# umodular_mega_shield_rev02.net
KiCad netlist of a schematic drawn in EAGLE
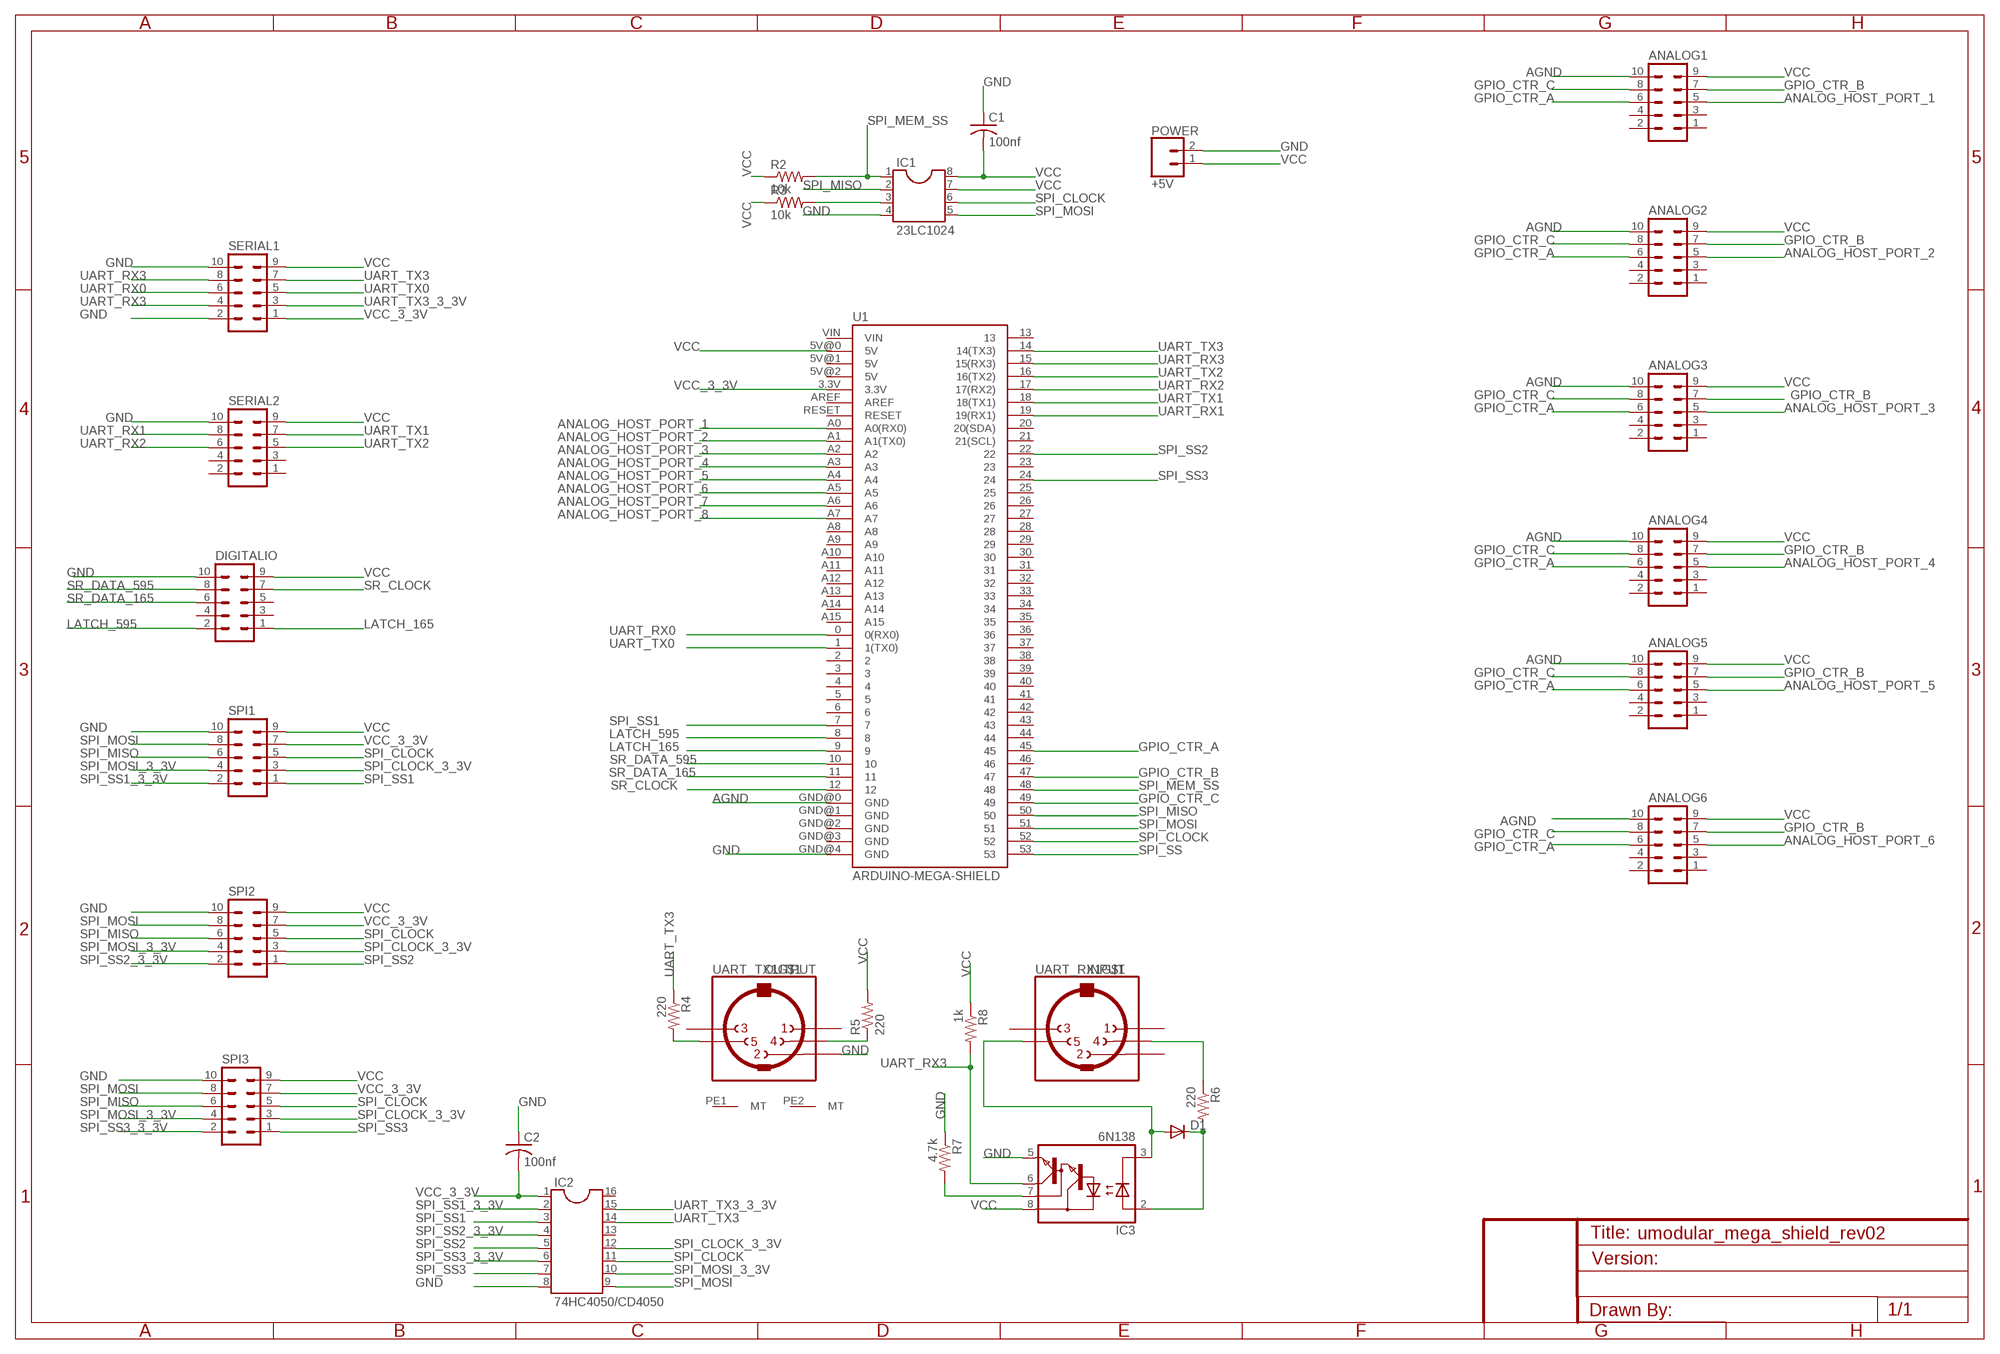
[diagram p0: schematic, sheet 1]

(export (version "E")
  (design (tool "Eeschema 10.0.6"))
  (components
    (comp (ref "ANALOG1")
      (value "MA05-2")
      (footprint "eagle-import:MA05-2")
      (libsource (lib "eagle-import") (part "MA05-2"))
    )
    (comp (ref "ANALOG2")
      (value "MA05-2")
      (footprint "eagle-import:MA05-2")
      (libsource (lib "eagle-import") (part "MA05-2"))
    )
    (comp (ref "ANALOG3")
      (value "MA05-2")
      (footprint "eagle-import:MA05-2")
      (libsource (lib "eagle-import") (part "MA05-2"))
    )
    (comp (ref "ANALOG4")
      (value "MA05-2")
      (footprint "eagle-import:MA05-2")
      (libsource (lib "eagle-import") (part "MA05-2"))
    )
    (comp (ref "ANALOG5")
      (value "MA05-2")
      (footprint "eagle-import:MA05-2")
      (libsource (lib "eagle-import") (part "MA05-2"))
    )
    (comp (ref "ANALOG6")
      (value "MA05-2")
      (footprint "eagle-import:MA05-2")
      (libsource (lib "eagle-import") (part "MA05-2"))
    )
    (comp (ref "C1")
      (value "100nf")
      (footprint "eagle-import:C050-024X044")
      (libsource (lib "eagle-import") (part "C-US050-024X044"))
    )
    (comp (ref "C2")
      (value "100nf")
      (footprint "eagle-import:C050-024X044")
      (libsource (lib "eagle-import") (part "C-US050-024X044"))
    )
    (comp (ref "D1")
      (value "1N4148DO35-7")
      (footprint "eagle-import:DO35-7")
      (libsource (lib "eagle-import") (part "1N4148DO35-7"))
    )
    (comp (ref "DIGITALIO")
      (value "MA05-2")
      (footprint "eagle-import:MA05-2")
      (libsource (lib "eagle-import") (part "MA05-2"))
    )
    (comp (ref "IC1")
      (value "23LC1024")
      (footprint "eagle-import:DIL08")
      (libsource (lib "eagle-import") (part "DIL8"))
    )
    (comp (ref "IC2")
      (value "74HC4050/CD4050")
      (footprint "eagle-import:DIL16")
      (libsource (lib "eagle-import") (part "DIL16"))
    )
    (comp (ref "IC3")
      (value "6N138")
      (footprint "eagle-import:DIL08")
      (fields (field (name "MF") "VISHAY/TELEFUNKEN"))
      (libsource (lib "eagle-import") (part "6N138"))
    )
    (comp (ref "POWER")
      (value "+5V")
      (footprint "eagle-import:1X02_LOCK_LONGPADS")
      (libsource (lib "eagle-import") (part "CONN_02LOCK_LONGPADS"))
    )
    (comp (ref "R2")
      (value "10k")
      (footprint "eagle-import:0204_7@1")
      (libsource (lib "eagle-import") (part "R-US_0204/7"))
    )
    (comp (ref "R3")
      (value "10k")
      (footprint "eagle-import:0204_7@1")
      (libsource (lib "eagle-import") (part "R-US_0204/7"))
    )
    (comp (ref "R4")
      (value "220")
      (footprint "eagle-import:0204_7@1")
      (libsource (lib "eagle-import") (part "R-US_0204/7"))
    )
    (comp (ref "R5")
      (value "220")
      (footprint "eagle-import:0204_7@1")
      (libsource (lib "eagle-import") (part "R-US_0204/7"))
    )
    (comp (ref "R6")
      (value "220")
      (footprint "eagle-import:0204_7@1")
      (libsource (lib "eagle-import") (part "R-US_0204/7"))
    )
    (comp (ref "R7")
      (value "4.7k")
      (footprint "eagle-import:0204_7@1")
      (libsource (lib "eagle-import") (part "R-US_0204/7"))
    )
    (comp (ref "R8")
      (value "1k")
      (footprint "eagle-import:0204_7@1")
      (libsource (lib "eagle-import") (part "R-US_0204/7"))
    )
    (comp (ref "SERIAL1")
      (value "MA05-2")
      (footprint "eagle-import:MA05-2")
      (libsource (lib "eagle-import") (part "MA05-2"))
    )
    (comp (ref "SERIAL2")
      (value "MA05-2")
      (footprint "eagle-import:MA05-2")
      (libsource (lib "eagle-import") (part "MA05-2"))
    )
    (comp (ref "SPI1")
      (value "MA05-2")
      (footprint "eagle-import:MA05-2")
      (libsource (lib "eagle-import") (part "MA05-2"))
    )
    (comp (ref "SPI2")
      (value "MA05-2")
      (footprint "eagle-import:MA05-2")
      (libsource (lib "eagle-import") (part "MA05-2"))
    )
    (comp (ref "SPI3")
      (value "MA05-2")
      (footprint "eagle-import:MA05-2")
      (libsource (lib "eagle-import") (part "MA05-2"))
    )
    (comp (ref "U1")
      (value "ARDUINO-MEGA-SHIELD")
      (footprint "eagle-import:ARDUINO_MEGA@1")
      (libsource (lib "eagle-import") (part "ARDUINO-MEGAFULL"))
    )
    (comp (ref "UART_RX1")
      (value "INPUT")
      (footprint "eagle-import:CP-2350")
      (libsource (lib "eagle-import") (part "MIDIJACK"))
    )
    (comp (ref "UART_TX1")
      (value "OUTPUT")
      (footprint "eagle-import:CP-2350")
      (libsource (lib "eagle-import") (part "MIDIJACK"))
    )
  )
  (nets
    (net (code "1") (name "/AGND") (class "Default")
      (node (ref "ANALOG1") (pin "10") (pinfunction "10_10") (pintype "passive"))
      (node (ref "ANALOG2") (pin "10") (pinfunction "10_10") (pintype "passive"))
      (node (ref "ANALOG3") (pin "10") (pinfunction "10_10") (pintype "passive"))
      (node (ref "ANALOG4") (pin "10") (pinfunction "10_10") (pintype "passive"))
      (node (ref "ANALOG5") (pin "10") (pinfunction "10_10") (pintype "passive"))
      (node (ref "ANALOG6") (pin "10") (pinfunction "10_10") (pintype "passive"))
      (node (ref "U1") (pin "GND@0") (pinfunction "GND_GND@0") (pintype "bidirectional"))
    )
    (net (code "2") (name "/ANALOG_HOST_PORT_1") (class "Default")
      (node (ref "ANALOG1") (pin "5") (pinfunction "5_5") (pintype "passive"))
      (node (ref "U1") (pin "A0") (pinfunction "A0(RX0)_A0") (pintype "bidirectional"))
    )
    (net (code "3") (name "/ANALOG_HOST_PORT_2") (class "Default")
      (node (ref "ANALOG2") (pin "5") (pinfunction "5_5") (pintype "passive"))
      (node (ref "U1") (pin "A1") (pinfunction "A1(TX0)_A1") (pintype "bidirectional"))
    )
    (net (code "4") (name "/ANALOG_HOST_PORT_3") (class "Default")
      (node (ref "ANALOG3") (pin "5") (pinfunction "5_5") (pintype "passive"))
      (node (ref "U1") (pin "A2") (pinfunction "A2_A2") (pintype "bidirectional"))
    )
    (net (code "5") (name "/ANALOG_HOST_PORT_4") (class "Default")
      (node (ref "ANALOG4") (pin "5") (pinfunction "5_5") (pintype "passive"))
      (node (ref "U1") (pin "A3") (pinfunction "A3_A3") (pintype "bidirectional"))
    )
    (net (code "6") (name "/ANALOG_HOST_PORT_5") (class "Default")
      (node (ref "ANALOG5") (pin "5") (pinfunction "5_5") (pintype "passive"))
      (node (ref "U1") (pin "A4") (pinfunction "A4_A4") (pintype "bidirectional"))
    )
    (net (code "7") (name "/ANALOG_HOST_PORT_6") (class "Default")
      (node (ref "ANALOG6") (pin "5") (pinfunction "5_5") (pintype "passive"))
      (node (ref "U1") (pin "A5") (pinfunction "A5_A5") (pintype "bidirectional"))
    )
    (net (code "8") (name "/ANALOG_HOST_PORT_7") (class "Default")
      (node (ref "U1") (pin "A6") (pinfunction "A6_A6") (pintype "bidirectional"))
    )
    (net (code "9") (name "/ANALOG_HOST_PORT_8") (class "Default")
      (node (ref "U1") (pin "A7") (pinfunction "A7_A7") (pintype "bidirectional"))
    )
    (net (code "10") (name "/GND") (class "Default")
      (node (ref "C1") (pin "1") (pinfunction "1_1") (pintype "passive"))
      (node (ref "C2") (pin "1") (pinfunction "1_1") (pintype "passive"))
      (node (ref "DIGITALIO") (pin "10") (pinfunction "10_10") (pintype "passive"))
      (node (ref "IC1") (pin "4") (pinfunction "4_4") (pintype "passive"))
      (node (ref "IC2") (pin "8") (pinfunction "8_8") (pintype "passive"))
      (node (ref "IC3") (pin "5") (pinfunction "GND_5") (pintype "passive"))
      (node (ref "POWER") (pin "2") (pinfunction "2_2") (pintype "passive"))
      (node (ref "R7") (pin "1") (pinfunction "1_1") (pintype "passive"))
      (node (ref "SERIAL1") (pin "10") (pinfunction "10_10") (pintype "passive"))
      (node (ref "SERIAL1") (pin "2") (pinfunction "2_2") (pintype "passive"))
      (node (ref "SERIAL2") (pin "10") (pinfunction "10_10") (pintype "passive"))
      (node (ref "SPI1") (pin "10") (pinfunction "10_10") (pintype "passive"))
      (node (ref "SPI2") (pin "10") (pinfunction "10_10") (pintype "passive"))
      (node (ref "SPI3") (pin "10") (pinfunction "10_10") (pintype "passive"))
      (node (ref "U1") (pin "GND@4") (pinfunction "GND_GND@4") (pintype "bidirectional"))
      (node (ref "UART_TX1") (pin "2") (pinfunction "2_2") (pintype "passive"))
    )
    (net (code "11") (name "/GPIO_CTR_A") (class "Default")
      (node (ref "ANALOG1") (pin "6") (pinfunction "6_6") (pintype "passive"))
      (node (ref "ANALOG2") (pin "6") (pinfunction "6_6") (pintype "passive"))
      (node (ref "ANALOG3") (pin "6") (pinfunction "6_6") (pintype "passive"))
      (node (ref "ANALOG4") (pin "6") (pinfunction "6_6") (pintype "passive"))
      (node (ref "ANALOG5") (pin "6") (pinfunction "6_6") (pintype "passive"))
      (node (ref "ANALOG6") (pin "6") (pinfunction "6_6") (pintype "passive"))
      (node (ref "U1") (pin "45") (pinfunction "45_45") (pintype "bidirectional"))
    )
    (net (code "12") (name "/GPIO_CTR_B") (class "Default")
      (node (ref "ANALOG1") (pin "7") (pinfunction "7_7") (pintype "passive"))
      (node (ref "ANALOG2") (pin "7") (pinfunction "7_7") (pintype "passive"))
      (node (ref "ANALOG3") (pin "7") (pinfunction "7_7") (pintype "passive"))
      (node (ref "ANALOG4") (pin "7") (pinfunction "7_7") (pintype "passive"))
      (node (ref "ANALOG5") (pin "7") (pinfunction "7_7") (pintype "passive"))
      (node (ref "ANALOG6") (pin "7") (pinfunction "7_7") (pintype "passive"))
      (node (ref "U1") (pin "47") (pinfunction "47_47") (pintype "bidirectional"))
    )
    (net (code "13") (name "/GPIO_CTR_C") (class "Default")
      (node (ref "ANALOG1") (pin "8") (pinfunction "8_8") (pintype "passive"))
      (node (ref "ANALOG2") (pin "8") (pinfunction "8_8") (pintype "passive"))
      (node (ref "ANALOG3") (pin "8") (pinfunction "8_8") (pintype "passive"))
      (node (ref "ANALOG4") (pin "8") (pinfunction "8_8") (pintype "passive"))
      (node (ref "ANALOG5") (pin "8") (pinfunction "8_8") (pintype "passive"))
      (node (ref "ANALOG6") (pin "8") (pinfunction "8_8") (pintype "passive"))
      (node (ref "U1") (pin "49") (pinfunction "49_49") (pintype "bidirectional"))
    )
    (net (code "14") (name "/LATCH_165") (class "Default")
      (node (ref "DIGITALIO") (pin "1") (pinfunction "1_1") (pintype "passive"))
      (node (ref "U1") (pin "9") (pinfunction "9_9") (pintype "bidirectional"))
    )
    (net (code "15") (name "/LATCH_595") (class "Default")
      (node (ref "DIGITALIO") (pin "2") (pinfunction "2_2") (pintype "passive"))
      (node (ref "U1") (pin "8") (pinfunction "8_8") (pintype "bidirectional"))
    )
    (net (code "16") (name "/SPI_CLOCK") (class "Default")
      (node (ref "IC1") (pin "6") (pinfunction "6_6") (pintype "passive"))
      (node (ref "IC2") (pin "11") (pinfunction "11_11") (pintype "passive"))
      (node (ref "SPI1") (pin "5") (pinfunction "5_5") (pintype "passive"))
      (node (ref "SPI2") (pin "5") (pinfunction "5_5") (pintype "passive"))
      (node (ref "SPI3") (pin "5") (pinfunction "5_5") (pintype "passive"))
      (node (ref "U1") (pin "52") (pinfunction "52_52") (pintype "bidirectional"))
    )
    (net (code "17") (name "/SPI_CLOCK_3_3V") (class "Default")
      (node (ref "IC2") (pin "12") (pinfunction "12_12") (pintype "passive"))
      (node (ref "SPI1") (pin "3") (pinfunction "3_3") (pintype "passive"))
      (node (ref "SPI2") (pin "3") (pinfunction "3_3") (pintype "passive"))
      (node (ref "SPI3") (pin "3") (pinfunction "3_3") (pintype "passive"))
    )
    (net (code "18") (name "/SPI_MEM_SS") (class "Default")
      (node (ref "IC1") (pin "1") (pinfunction "1_1") (pintype "passive"))
      (node (ref "R2") (pin "2") (pinfunction "2_2") (pintype "passive"))
      (node (ref "U1") (pin "48") (pinfunction "48_48") (pintype "bidirectional"))
    )
    (net (code "19") (name "/SPI_MISO") (class "Default")
      (node (ref "IC1") (pin "2") (pinfunction "2_2") (pintype "passive"))
      (node (ref "SPI1") (pin "6") (pinfunction "6_6") (pintype "passive"))
      (node (ref "SPI2") (pin "6") (pinfunction "6_6") (pintype "passive"))
      (node (ref "SPI3") (pin "6") (pinfunction "6_6") (pintype "passive"))
      (node (ref "U1") (pin "50") (pinfunction "50_50") (pintype "bidirectional"))
    )
    (net (code "20") (name "/SPI_MOSI") (class "Default")
      (node (ref "IC1") (pin "5") (pinfunction "5_5") (pintype "passive"))
      (node (ref "IC2") (pin "9") (pinfunction "9_9") (pintype "passive"))
      (node (ref "SPI1") (pin "8") (pinfunction "8_8") (pintype "passive"))
      (node (ref "SPI2") (pin "8") (pinfunction "8_8") (pintype "passive"))
      (node (ref "SPI3") (pin "8") (pinfunction "8_8") (pintype "passive"))
      (node (ref "U1") (pin "51") (pinfunction "51_51") (pintype "bidirectional"))
    )
    (net (code "21") (name "/SPI_MOSI_3_3V") (class "Default")
      (node (ref "IC2") (pin "10") (pinfunction "10_10") (pintype "passive"))
      (node (ref "SPI1") (pin "4") (pinfunction "4_4") (pintype "passive"))
      (node (ref "SPI2") (pin "4") (pinfunction "4_4") (pintype "passive"))
      (node (ref "SPI3") (pin "4") (pinfunction "4_4") (pintype "passive"))
    )
    (net (code "22") (name "/SPI_SS") (class "Default")
      (node (ref "U1") (pin "53") (pinfunction "53_53") (pintype "bidirectional"))
    )
    (net (code "23") (name "/SPI_SS1") (class "Default")
      (node (ref "IC2") (pin "3") (pinfunction "3_3") (pintype "passive"))
      (node (ref "SPI1") (pin "1") (pinfunction "1_1") (pintype "passive"))
      (node (ref "U1") (pin "7") (pinfunction "7_7") (pintype "bidirectional"))
    )
    (net (code "24") (name "/SPI_SS1_3_3V") (class "Default")
      (node (ref "IC2") (pin "2") (pinfunction "2_2") (pintype "passive"))
      (node (ref "SPI1") (pin "2") (pinfunction "2_2") (pintype "passive"))
    )
    (net (code "25") (name "/SPI_SS2") (class "Default")
      (node (ref "IC2") (pin "5") (pinfunction "5_5") (pintype "passive"))
      (node (ref "SPI2") (pin "1") (pinfunction "1_1") (pintype "passive"))
      (node (ref "U1") (pin "22") (pinfunction "22_22") (pintype "bidirectional"))
    )
    (net (code "26") (name "/SPI_SS2_3_3V") (class "Default")
      (node (ref "IC2") (pin "4") (pinfunction "4_4") (pintype "passive"))
      (node (ref "SPI2") (pin "2") (pinfunction "2_2") (pintype "passive"))
    )
    (net (code "27") (name "/SPI_SS3") (class "Default")
      (node (ref "IC2") (pin "7") (pinfunction "7_7") (pintype "passive"))
      (node (ref "SPI3") (pin "1") (pinfunction "1_1") (pintype "passive"))
      (node (ref "U1") (pin "24") (pinfunction "24_24") (pintype "bidirectional"))
    )
    (net (code "28") (name "/SPI_SS3_3_3V") (class "Default")
      (node (ref "IC2") (pin "6") (pinfunction "6_6") (pintype "passive"))
      (node (ref "SPI3") (pin "2") (pinfunction "2_2") (pintype "passive"))
    )
    (net (code "29") (name "/SR_CLOCK") (class "Default")
      (node (ref "DIGITALIO") (pin "7") (pinfunction "7_7") (pintype "passive"))
      (node (ref "U1") (pin "12") (pinfunction "12_12") (pintype "bidirectional"))
    )
    (net (code "30") (name "/SR_DATA_165") (class "Default")
      (node (ref "DIGITALIO") (pin "6") (pinfunction "6_6") (pintype "passive"))
      (node (ref "U1") (pin "11") (pinfunction "11_11") (pintype "bidirectional"))
    )
    (net (code "31") (name "/SR_DATA_595") (class "Default")
      (node (ref "DIGITALIO") (pin "8") (pinfunction "8_8") (pintype "passive"))
      (node (ref "U1") (pin "10") (pinfunction "10_10") (pintype "bidirectional"))
    )
    (net (code "32") (name "/UART_RX0") (class "Default")
      (node (ref "SERIAL1") (pin "6") (pinfunction "6_6") (pintype "passive"))
      (node (ref "U1") (pin "0") (pinfunction "0(RX0)_0") (pintype "bidirectional"))
    )
    (net (code "33") (name "/UART_RX1") (class "Default")
      (node (ref "SERIAL2") (pin "8") (pinfunction "8_8") (pintype "passive"))
      (node (ref "U1") (pin "19") (pinfunction "19(RX1)_19") (pintype "bidirectional"))
    )
    (net (code "34") (name "/UART_RX2") (class "Default")
      (node (ref "SERIAL2") (pin "6") (pinfunction "6_6") (pintype "passive"))
      (node (ref "U1") (pin "17") (pinfunction "17(RX2)_17") (pintype "bidirectional"))
    )
    (net (code "35") (name "/UART_RX3") (class "Default")
      (node (ref "IC3") (pin "6") (pinfunction "VO_6") (pintype "passive"))
      (node (ref "R8") (pin "2") (pinfunction "2_2") (pintype "passive"))
      (node (ref "SERIAL1") (pin "4") (pinfunction "4_4") (pintype "passive"))
      (node (ref "SERIAL1") (pin "8") (pinfunction "8_8") (pintype "passive"))
      (node (ref "U1") (pin "15") (pinfunction "15(RX3)_15") (pintype "bidirectional"))
    )
    (net (code "36") (name "/UART_TX0") (class "Default")
      (node (ref "SERIAL1") (pin "5") (pinfunction "5_5") (pintype "passive"))
      (node (ref "U1") (pin "1") (pinfunction "1(TX0)_1") (pintype "bidirectional"))
    )
    (net (code "37") (name "/UART_TX1") (class "Default")
      (node (ref "SERIAL2") (pin "7") (pinfunction "7_7") (pintype "passive"))
      (node (ref "U1") (pin "18") (pinfunction "18(TX1)_18") (pintype "bidirectional"))
    )
    (net (code "38") (name "/UART_TX2") (class "Default")
      (node (ref "SERIAL2") (pin "5") (pinfunction "5_5") (pintype "passive"))
      (node (ref "U1") (pin "16") (pinfunction "16(TX2)_16") (pintype "bidirectional"))
    )
    (net (code "39") (name "/UART_TX3") (class "Default")
      (node (ref "IC2") (pin "14") (pinfunction "14_14") (pintype "passive"))
      (node (ref "R4") (pin "1") (pinfunction "1_1") (pintype "passive"))
      (node (ref "SERIAL1") (pin "7") (pinfunction "7_7") (pintype "passive"))
      (node (ref "U1") (pin "14") (pinfunction "14(TX3)_14") (pintype "bidirectional"))
    )
    (net (code "40") (name "/UART_TX3_3_3V") (class "Default")
      (node (ref "IC2") (pin "15") (pinfunction "15_15") (pintype "passive"))
      (node (ref "SERIAL1") (pin "3") (pinfunction "3_3") (pintype "passive"))
    )
    (net (code "41") (name "/VCC") (class "Default")
      (node (ref "ANALOG1") (pin "9") (pinfunction "9_9") (pintype "passive"))
      (node (ref "ANALOG2") (pin "9") (pinfunction "9_9") (pintype "passive"))
      (node (ref "ANALOG3") (pin "9") (pinfunction "9_9") (pintype "passive"))
      (node (ref "ANALOG4") (pin "9") (pinfunction "9_9") (pintype "passive"))
      (node (ref "ANALOG5") (pin "9") (pinfunction "9_9") (pintype "passive"))
      (node (ref "ANALOG6") (pin "9") (pinfunction "9_9") (pintype "passive"))
      (node (ref "C1") (pin "2") (pinfunction "2_2") (pintype "passive"))
      (node (ref "DIGITALIO") (pin "9") (pinfunction "9_9") (pintype "passive"))
      (node (ref "IC1") (pin "7") (pinfunction "7_7") (pintype "passive"))
      (node (ref "IC1") (pin "8") (pinfunction "8_8") (pintype "passive"))
      (node (ref "IC3") (pin "8") (pinfunction "VCC_8") (pintype "passive"))
      (node (ref "POWER") (pin "1") (pinfunction "1_1") (pintype "passive"))
      (node (ref "R2") (pin "1") (pinfunction "1_1") (pintype "passive"))
      (node (ref "R3") (pin "1") (pinfunction "1_1") (pintype "passive"))
      (node (ref "R5") (pin "2") (pinfunction "2_2") (pintype "passive"))
      (node (ref "R8") (pin "1") (pinfunction "1_1") (pintype "passive"))
      (node (ref "SERIAL1") (pin "9") (pinfunction "9_9") (pintype "passive"))
      (node (ref "SERIAL2") (pin "9") (pinfunction "9_9") (pintype "passive"))
      (node (ref "SPI1") (pin "9") (pinfunction "9_9") (pintype "passive"))
      (node (ref "SPI2") (pin "9") (pinfunction "9_9") (pintype "passive"))
      (node (ref "SPI3") (pin "9") (pinfunction "9_9") (pintype "passive"))
      (node (ref "U1") (pin "5V@0") (pinfunction "5V_5V@0") (pintype "bidirectional"))
    )
    (net (code "42") (name "/VCC_3_3V") (class "Default")
      (node (ref "C2") (pin "2") (pinfunction "2_2") (pintype "passive"))
      (node (ref "IC2") (pin "1") (pinfunction "1_1") (pintype "passive"))
      (node (ref "SERIAL1") (pin "1") (pinfunction "1_1") (pintype "passive"))
      (node (ref "SPI1") (pin "7") (pinfunction "7_7") (pintype "passive"))
      (node (ref "SPI2") (pin "7") (pinfunction "7_7") (pintype "passive"))
      (node (ref "SPI3") (pin "7") (pinfunction "7_7") (pintype "passive"))
      (node (ref "U1") (pin "3.3V") (pinfunction "3.3V_3.3V") (pintype "bidirectional"))
    )
    (net (code "43") (name "Net-(IC1-Pad3)") (class "Default")
      (node (ref "IC1") (pin "3") (pinfunction "3_3") (pintype "passive"))
      (node (ref "R3") (pin "2") (pinfunction "2_2") (pintype "passive"))
    )
    (net (code "44") (name "Net-(IC3-A)") (class "Default")
      (node (ref "D1") (pin "C") (pinfunction "C_C") (pintype "passive"))
      (node (ref "IC3") (pin "2") (pinfunction "A_2") (pintype "passive"))
      (node (ref "R6") (pin "2") (pinfunction "2_2") (pintype "passive"))
    )
    (net (code "45") (name "Net-(IC3-C)") (class "Default")
      (node (ref "D1") (pin "A") (pinfunction "A_A") (pintype "passive"))
      (node (ref "IC3") (pin "3") (pinfunction "C_3") (pintype "passive"))
      (node (ref "UART_RX1") (pin "5") (pinfunction "5_5") (pintype "passive"))
    )
    (net (code "46") (name "Net-(IC3-VB)") (class "Default")
      (node (ref "IC3") (pin "7") (pinfunction "VB_7") (pintype "passive"))
      (node (ref "R7") (pin "2") (pinfunction "2_2") (pintype "passive"))
    )
    (net (code "47") (name "Net-(R4-Pad2)") (class "Default")
      (node (ref "R4") (pin "2") (pinfunction "2_2") (pintype "passive"))
      (node (ref "UART_TX1") (pin "5") (pinfunction "5_5") (pintype "passive"))
    )
    (net (code "48") (name "Net-(R5-Pad1)") (class "Default")
      (node (ref "R5") (pin "1") (pinfunction "1_1") (pintype "passive"))
      (node (ref "UART_TX1") (pin "4") (pinfunction "4_4") (pintype "passive"))
    )
    (net (code "49") (name "Net-(R6-Pad1)") (class "Default")
      (node (ref "R6") (pin "1") (pinfunction "1_1") (pintype "passive"))
      (node (ref "UART_RX1") (pin "4") (pinfunction "4_4") (pintype "passive"))
    )
    (net (code "50") (name "unconnected-(ANALOG1-Pad1)") (class "Default")
      (node (ref "ANALOG1") (pin "1") (pinfunction "1_1") (pintype "passive"))
    )
    (net (code "51") (name "unconnected-(ANALOG1-Pad2)") (class "Default")
      (node (ref "ANALOG1") (pin "2") (pinfunction "2_2") (pintype "passive"))
    )
    (net (code "52") (name "unconnected-(ANALOG1-Pad3)") (class "Default")
      (node (ref "ANALOG1") (pin "3") (pinfunction "3_3") (pintype "passive"))
    )
    (net (code "53") (name "unconnected-(ANALOG1-Pad4)") (class "Default")
      (node (ref "ANALOG1") (pin "4") (pinfunction "4_4") (pintype "passive"))
    )
    (net (code "54") (name "unconnected-(ANALOG2-Pad1)") (class "Default")
      (node (ref "ANALOG2") (pin "1") (pinfunction "1_1") (pintype "passive"))
    )
    (net (code "55") (name "unconnected-(ANALOG2-Pad2)") (class "Default")
      (node (ref "ANALOG2") (pin "2") (pinfunction "2_2") (pintype "passive"))
    )
    (net (code "56") (name "unconnected-(ANALOG2-Pad3)") (class "Default")
      (node (ref "ANALOG2") (pin "3") (pinfunction "3_3") (pintype "passive"))
    )
    (net (code "57") (name "unconnected-(ANALOG2-Pad4)") (class "Default")
      (node (ref "ANALOG2") (pin "4") (pinfunction "4_4") (pintype "passive"))
    )
    (net (code "58") (name "unconnected-(ANALOG3-Pad1)") (class "Default")
      (node (ref "ANALOG3") (pin "1") (pinfunction "1_1") (pintype "passive"))
    )
    (net (code "59") (name "unconnected-(ANALOG3-Pad2)") (class "Default")
      (node (ref "ANALOG3") (pin "2") (pinfunction "2_2") (pintype "passive"))
    )
    (net (code "60") (name "unconnected-(ANALOG3-Pad3)") (class "Default")
      (node (ref "ANALOG3") (pin "3") (pinfunction "3_3") (pintype "passive"))
    )
    (net (code "61") (name "unconnected-(ANALOG3-Pad4)") (class "Default")
      (node (ref "ANALOG3") (pin "4") (pinfunction "4_4") (pintype "passive"))
    )
    (net (code "62") (name "unconnected-(ANALOG4-Pad1)") (class "Default")
      (node (ref "ANALOG4") (pin "1") (pinfunction "1_1") (pintype "passive"))
    )
    (net (code "63") (name "unconnected-(ANALOG4-Pad2)") (class "Default")
      (node (ref "ANALOG4") (pin "2") (pinfunction "2_2") (pintype "passive"))
    )
    (net (code "64") (name "unconnected-(ANALOG4-Pad3)") (class "Default")
      (node (ref "ANALOG4") (pin "3") (pinfunction "3_3") (pintype "passive"))
    )
    (net (code "65") (name "unconnected-(ANALOG4-Pad4)") (class "Default")
      (node (ref "ANALOG4") (pin "4") (pinfunction "4_4") (pintype "passive"))
    )
    (net (code "66") (name "unconnected-(ANALOG5-Pad1)") (class "Default")
      (node (ref "ANALOG5") (pin "1") (pinfunction "1_1") (pintype "passive"))
    )
    (net (code "67") (name "unconnected-(ANALOG5-Pad2)") (class "Default")
      (node (ref "ANALOG5") (pin "2") (pinfunction "2_2") (pintype "passive"))
    )
    (net (code "68") (name "unconnected-(ANALOG5-Pad3)") (class "Default")
      (node (ref "ANALOG5") (pin "3") (pinfunction "3_3") (pintype "passive"))
    )
    (net (code "69") (name "unconnected-(ANALOG5-Pad4)") (class "Default")
      (node (ref "ANALOG5") (pin "4") (pinfunction "4_4") (pintype "passive"))
    )
    (net (code "70") (name "unconnected-(ANALOG6-Pad1)") (class "Default")
      (node (ref "ANALOG6") (pin "1") (pinfunction "1_1") (pintype "passive"))
    )
    (net (code "71") (name "unconnected-(ANALOG6-Pad2)") (class "Default")
      (node (ref "ANALOG6") (pin "2") (pinfunction "2_2") (pintype "passive"))
    )
    (net (code "72") (name "unconnected-(ANALOG6-Pad3)") (class "Default")
      (node (ref "ANALOG6") (pin "3") (pinfunction "3_3") (pintype "passive"))
    )
    (net (code "73") (name "unconnected-(ANALOG6-Pad4)") (class "Default")
      (node (ref "ANALOG6") (pin "4") (pinfunction "4_4") (pintype "passive"))
    )
    (net (code "74") (name "unconnected-(DIGITALIO-Pad3)") (class "Default")
      (node (ref "DIGITALIO") (pin "3") (pinfunction "3_3") (pintype "passive"))
    )
    (net (code "75") (name "unconnected-(DIGITALIO-Pad4)") (class "Default")
      (node (ref "DIGITALIO") (pin "4") (pinfunction "4_4") (pintype "passive"))
    )
    (net (code "76") (name "unconnected-(DIGITALIO-Pad5)") (class "Default")
      (node (ref "DIGITALIO") (pin "5") (pinfunction "5_5") (pintype "passive"))
    )
    (net (code "77") (name "unconnected-(IC2-Pad13)") (class "Default")
      (node (ref "IC2") (pin "13") (pinfunction "13_13") (pintype "passive"))
    )
    (net (code "78") (name "unconnected-(IC2-Pad16)") (class "Default")
      (node (ref "IC2") (pin "16") (pinfunction "16_16") (pintype "passive"))
    )
    (net (code "79") (name "unconnected-(SERIAL2-Pad1)") (class "Default")
      (node (ref "SERIAL2") (pin "1") (pinfunction "1_1") (pintype "passive"))
    )
    (net (code "80") (name "unconnected-(SERIAL2-Pad2)") (class "Default")
      (node (ref "SERIAL2") (pin "2") (pinfunction "2_2") (pintype "passive"))
    )
    (net (code "81") (name "unconnected-(SERIAL2-Pad3)") (class "Default")
      (node (ref "SERIAL2") (pin "3") (pinfunction "3_3") (pintype "passive"))
    )
    (net (code "82") (name "unconnected-(SERIAL2-Pad4)") (class "Default")
      (node (ref "SERIAL2") (pin "4") (pinfunction "4_4") (pintype "passive"))
    )
    (net (code "83") (name "unconnected-(U1-5V-Pad5V@1)") (class "Default")
      (node (ref "U1") (pin "5V@1") (pinfunction "5V_5V@1") (pintype "bidirectional"))
    )
    (net (code "84") (name "unconnected-(U1-5V-Pad5V@2)") (class "Default")
      (node (ref "U1") (pin "5V@2") (pinfunction "5V_5V@2") (pintype "bidirectional"))
    )
    (net (code "85") (name "unconnected-(U1-20(SDA)-Pad20)") (class "Default")
      (node (ref "U1") (pin "20") (pinfunction "20(SDA)_20") (pintype "bidirectional"))
    )
    (net (code "86") (name "unconnected-(U1-21(SCL)-Pad21)") (class "Default")
      (node (ref "U1") (pin "21") (pinfunction "21(SCL)_21") (pintype "bidirectional"))
    )
    (net (code "87") (name "unconnected-(U1-GND-PadGND@1)") (class "Default")
      (node (ref "U1") (pin "GND@1") (pinfunction "GND_GND@1") (pintype "bidirectional"))
    )
    (net (code "88") (name "unconnected-(U1-GND-PadGND@2)") (class "Default")
      (node (ref "U1") (pin "GND@2") (pinfunction "GND_GND@2") (pintype "bidirectional"))
    )
    (net (code "89") (name "unconnected-(U1-GND-PadGND@3)") (class "Default")
      (node (ref "U1") (pin "GND@3") (pinfunction "GND_GND@3") (pintype "bidirectional"))
    )
    (net (code "90") (name "unconnected-(U1-Pad2)") (class "Default")
      (node (ref "U1") (pin "2") (pinfunction "2_2") (pintype "bidirectional"))
    )
    (net (code "91") (name "unconnected-(U1-Pad3)") (class "Default")
      (node (ref "U1") (pin "3") (pinfunction "3_3") (pintype "bidirectional"))
    )
    (net (code "92") (name "unconnected-(U1-Pad4)") (class "Default")
      (node (ref "U1") (pin "4") (pinfunction "4_4") (pintype "bidirectional"))
    )
    (net (code "93") (name "unconnected-(U1-Pad5)") (class "Default")
      (node (ref "U1") (pin "5") (pinfunction "5_5") (pintype "bidirectional"))
    )
    (net (code "94") (name "unconnected-(U1-Pad6)") (class "Default")
      (node (ref "U1") (pin "6") (pinfunction "6_6") (pintype "bidirectional"))
    )
    (net (code "95") (name "unconnected-(U1-Pad13)") (class "Default")
      (node (ref "U1") (pin "13") (pinfunction "13_13") (pintype "bidirectional"))
    )
    (net (code "96") (name "unconnected-(U1-Pad23)") (class "Default")
      (node (ref "U1") (pin "23") (pinfunction "23_23") (pintype "bidirectional"))
    )
    (net (code "97") (name "unconnected-(U1-Pad25)") (class "Default")
      (node (ref "U1") (pin "25") (pinfunction "25_25") (pintype "bidirectional"))
    )
    (net (code "98") (name "unconnected-(U1-Pad26)") (class "Default")
      (node (ref "U1") (pin "26") (pinfunction "26_26") (pintype "bidirectional"))
    )
    (net (code "99") (name "unconnected-(U1-Pad27)") (class "Default")
      (node (ref "U1") (pin "27") (pinfunction "27_27") (pintype "bidirectional"))
    )
    (net (code "100") (name "unconnected-(U1-Pad28)") (class "Default")
      (node (ref "U1") (pin "28") (pinfunction "28_28") (pintype "bidirectional"))
    )
    (net (code "101") (name "unconnected-(U1-Pad29)") (class "Default")
      (node (ref "U1") (pin "29") (pinfunction "29_29") (pintype "bidirectional"))
    )
    (net (code "102") (name "unconnected-(U1-Pad30)") (class "Default")
      (node (ref "U1") (pin "30") (pinfunction "30_30") (pintype "bidirectional"))
    )
    (net (code "103") (name "unconnected-(U1-Pad31)") (class "Default")
      (node (ref "U1") (pin "31") (pinfunction "31_31") (pintype "bidirectional"))
    )
    (net (code "104") (name "unconnected-(U1-Pad32)") (class "Default")
      (node (ref "U1") (pin "32") (pinfunction "32_32") (pintype "bidirectional"))
    )
    (net (code "105") (name "unconnected-(U1-Pad33)") (class "Default")
      (node (ref "U1") (pin "33") (pinfunction "33_33") (pintype "bidirectional"))
    )
    (net (code "106") (name "unconnected-(U1-Pad34)") (class "Default")
      (node (ref "U1") (pin "34") (pinfunction "34_34") (pintype "bidirectional"))
    )
    (net (code "107") (name "unconnected-(U1-Pad35)") (class "Default")
      (node (ref "U1") (pin "35") (pinfunction "35_35") (pintype "bidirectional"))
    )
    (net (code "108") (name "unconnected-(U1-Pad36)") (class "Default")
      (node (ref "U1") (pin "36") (pinfunction "36_36") (pintype "bidirectional"))
    )
    (net (code "109") (name "unconnected-(U1-Pad37)") (class "Default")
      (node (ref "U1") (pin "37") (pinfunction "37_37") (pintype "bidirectional"))
    )
    (net (code "110") (name "unconnected-(U1-Pad38)") (class "Default")
      (node (ref "U1") (pin "38") (pinfunction "38_38") (pintype "bidirectional"))
    )
    (net (code "111") (name "unconnected-(U1-Pad39)") (class "Default")
      (node (ref "U1") (pin "39") (pinfunction "39_39") (pintype "bidirectional"))
    )
    (net (code "112") (name "unconnected-(U1-Pad40)") (class "Default")
      (node (ref "U1") (pin "40") (pinfunction "40_40") (pintype "bidirectional"))
    )
    (net (code "113") (name "unconnected-(U1-Pad41)") (class "Default")
      (node (ref "U1") (pin "41") (pinfunction "41_41") (pintype "bidirectional"))
    )
    (net (code "114") (name "unconnected-(U1-Pad42)") (class "Default")
      (node (ref "U1") (pin "42") (pinfunction "42_42") (pintype "bidirectional"))
    )
    (net (code "115") (name "unconnected-(U1-Pad43)") (class "Default")
      (node (ref "U1") (pin "43") (pinfunction "43_43") (pintype "bidirectional"))
    )
    (net (code "116") (name "unconnected-(U1-Pad44)") (class "Default")
      (node (ref "U1") (pin "44") (pinfunction "44_44") (pintype "bidirectional"))
    )
    (net (code "117") (name "unconnected-(U1-Pad46)") (class "Default")
      (node (ref "U1") (pin "46") (pinfunction "46_46") (pintype "bidirectional"))
    )
    (net (code "118") (name "unconnected-(U1-PadA8)") (class "Default")
      (node (ref "U1") (pin "A8") (pinfunction "A8_A8") (pintype "bidirectional"))
    )
    (net (code "119") (name "unconnected-(U1-PadA9)") (class "Default")
      (node (ref "U1") (pin "A9") (pinfunction "A9_A9") (pintype "bidirectional"))
    )
    (net (code "120") (name "unconnected-(U1-PadA10)") (class "Default")
      (node (ref "U1") (pin "A10") (pinfunction "A10_A10") (pintype "bidirectional"))
    )
    (net (code "121") (name "unconnected-(U1-PadA11)") (class "Default")
      (node (ref "U1") (pin "A11") (pinfunction "A11_A11") (pintype "bidirectional"))
    )
    (net (code "122") (name "unconnected-(U1-PadA12)") (class "Default")
      (node (ref "U1") (pin "A12") (pinfunction "A12_A12") (pintype "bidirectional"))
    )
    (net (code "123") (name "unconnected-(U1-PadA13)") (class "Default")
      (node (ref "U1") (pin "A13") (pinfunction "A13_A13") (pintype "bidirectional"))
    )
    (net (code "124") (name "unconnected-(U1-PadA14)") (class "Default")
      (node (ref "U1") (pin "A14") (pinfunction "A14_A14") (pintype "bidirectional"))
    )
    (net (code "125") (name "unconnected-(U1-PadA15)") (class "Default")
      (node (ref "U1") (pin "A15") (pinfunction "A15_A15") (pintype "bidirectional"))
    )
    (net (code "126") (name "unconnected-(U1-PadAREF)") (class "Default")
      (node (ref "U1") (pin "AREF") (pinfunction "AREF_AREF") (pintype "bidirectional"))
    )
    (net (code "127") (name "unconnected-(U1-PadRESET)") (class "Default")
      (node (ref "U1") (pin "RESET") (pinfunction "RESET_RESET") (pintype "bidirectional"))
    )
    (net (code "128") (name "unconnected-(U1-PadVIN)") (class "Default")
      (node (ref "U1") (pin "VIN") (pinfunction "VIN_VIN") (pintype "bidirectional"))
    )
    (net (code "129") (name "unconnected-(UART_RX1-Pad1)") (class "Default")
      (node (ref "UART_RX1") (pin "1") (pinfunction "1_1") (pintype "passive"))
    )
    (net (code "130") (name "unconnected-(UART_RX1-Pad2)") (class "Default")
      (node (ref "UART_RX1") (pin "2") (pinfunction "2_2") (pintype "passive"))
    )
    (net (code "131") (name "unconnected-(UART_RX1-Pad3)") (class "Default")
      (node (ref "UART_RX1") (pin "3") (pinfunction "3_3") (pintype "passive"))
    )
    (net (code "132") (name "unconnected-(UART_TX1-Pad1)") (class "Default")
      (node (ref "UART_TX1") (pin "1") (pinfunction "1_1") (pintype "passive"))
    )
    (net (code "133") (name "unconnected-(UART_TX1-Pad3)") (class "Default")
      (node (ref "UART_TX1") (pin "3") (pinfunction "3_3") (pintype "passive"))
    )
    (net (code "134") (name "unconnected-(UART_TX1D-MT-PadPE1)") (class "Default")
      (node (ref "UART_TX1") (pin "PE1") (pinfunction "MT_PE1") (pintype "passive"))
    )
    (net (code "135") (name "unconnected-(UART_TX1E-MT-PadPE2)") (class "Default")
      (node (ref "UART_TX1") (pin "PE2") (pinfunction "MT_PE2") (pintype "passive"))
    )
  )
)
